# Blueshift_V3.net
KiCad netlist of a schematic drawn in EAGLE
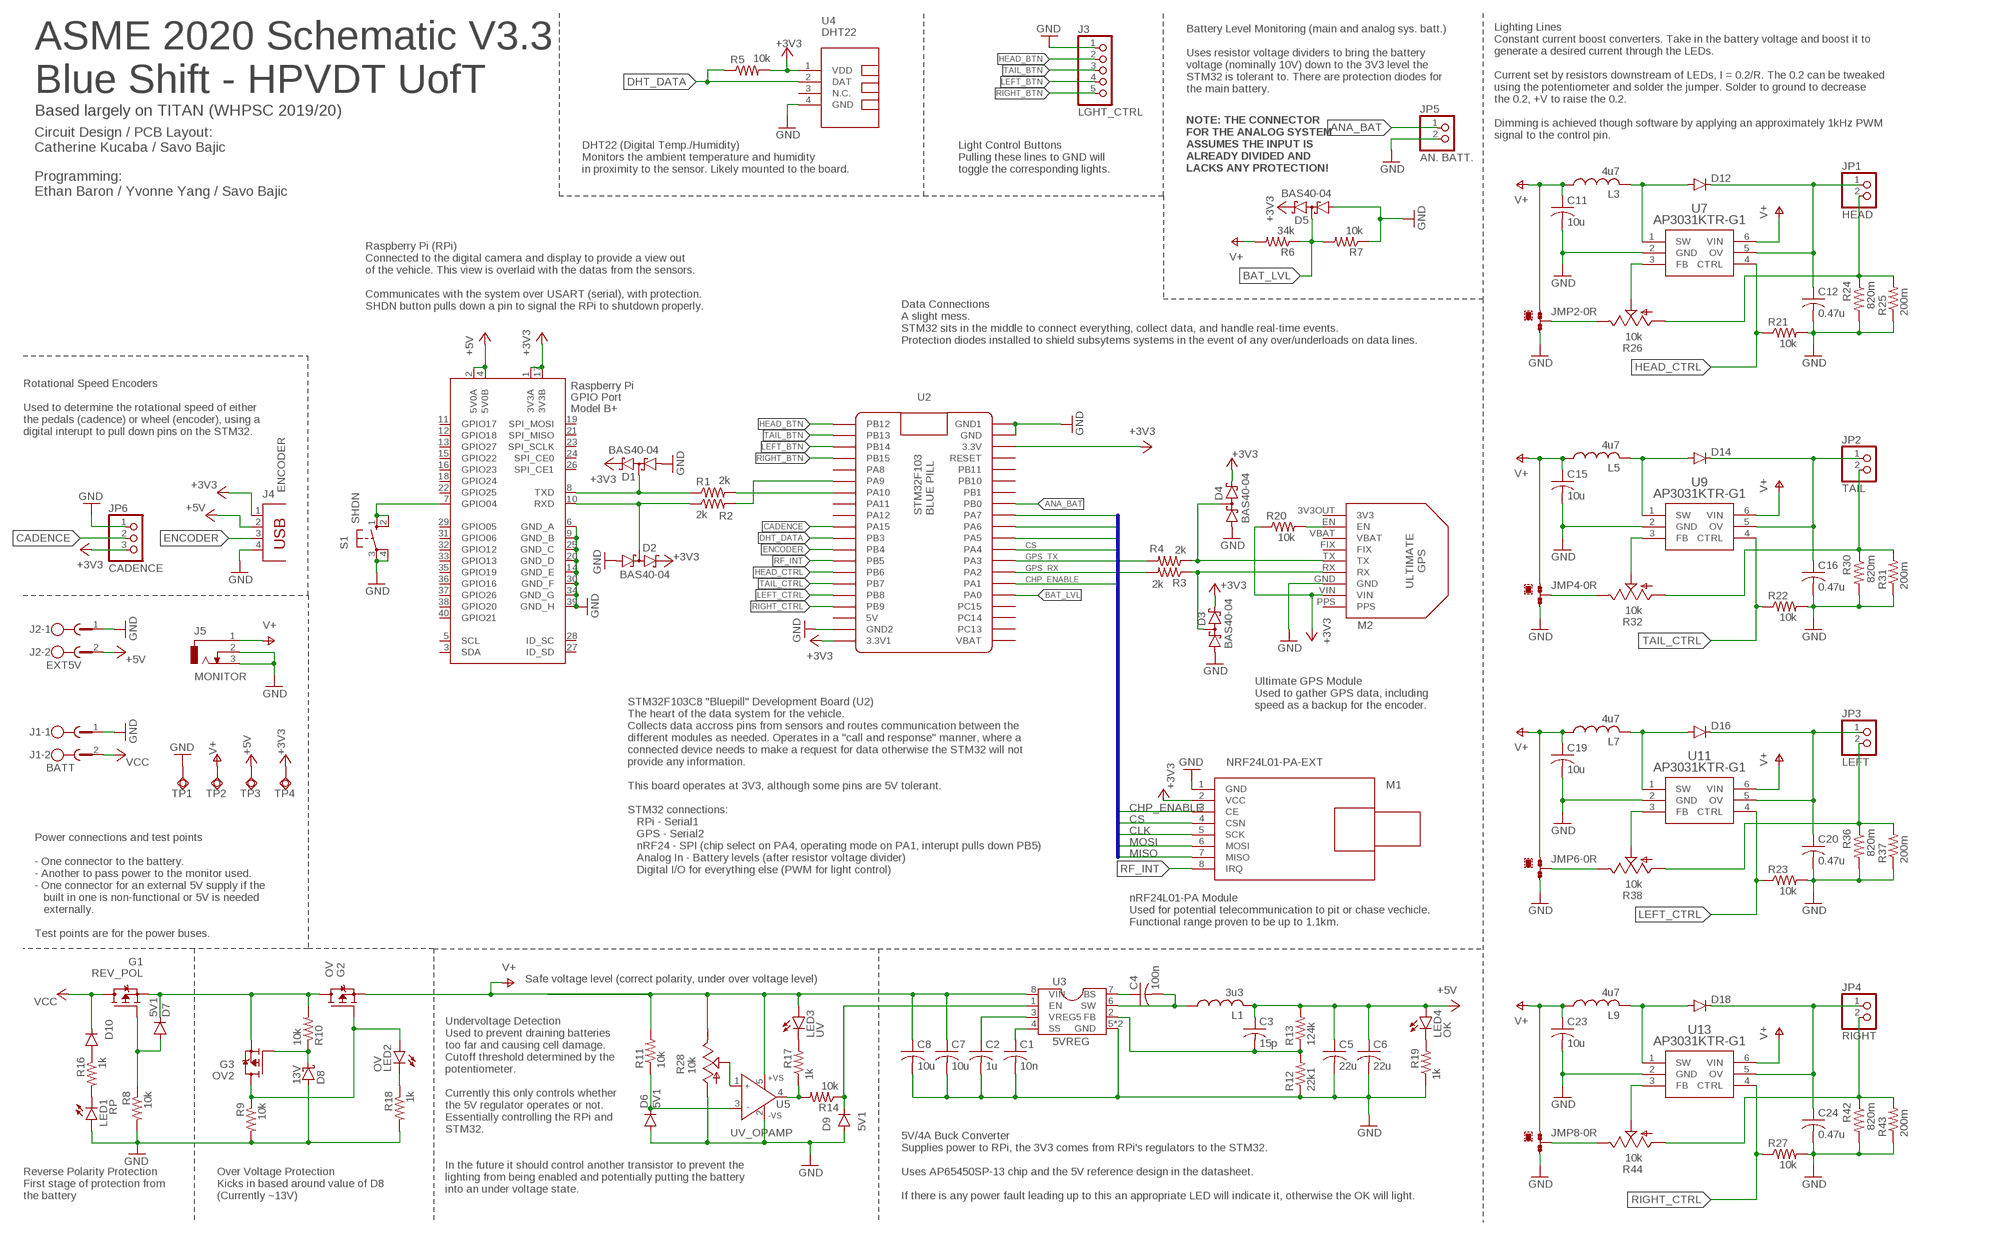
[diagram p0: schematic, sheet 1]

(export (version "E")
  (design (tool "Eeschema 10.0.6"))
  (components
    (comp (ref "C1")
      (value "10n")
      (footprint "eagle-import:C0402")
      (libsource (lib "eagle-import") (part "C-USC0402"))
    )
    (comp (ref "C2")
      (value "1u")
      (footprint "eagle-import:C0402")
      (libsource (lib "eagle-import") (part "C-USC0402"))
    )
    (comp (ref "C3")
      (value "15p")
      (footprint "eagle-import:C0402")
      (libsource (lib "eagle-import") (part "C-USC0402"))
    )
    (comp (ref "C4")
      (value "100n")
      (footprint "eagle-import:C0402")
      (libsource (lib "eagle-import") (part "C-USC0402"))
    )
    (comp (ref "C5")
      (value "22u")
      (footprint "eagle-import:C0805")
      (libsource (lib "eagle-import") (part "C-USC0805"))
    )
    (comp (ref "C6")
      (value "22u")
      (footprint "eagle-import:C0805")
      (libsource (lib "eagle-import") (part "C-USC0805"))
    )
    (comp (ref "C7")
      (value "10u")
      (footprint "eagle-import:C0805")
      (libsource (lib "eagle-import") (part "C-USC0805"))
    )
    (comp (ref "C8")
      (value "10u")
      (footprint "eagle-import:C0805")
      (libsource (lib "eagle-import") (part "C-USC0805"))
    )
    (comp (ref "C11")
      (value "10u")
      (footprint "eagle-import:C1206K")
      (libsource (lib "eagle-import") (part "C-USC1206K"))
    )
    (comp (ref "C12")
      (value "0.47u")
      (footprint "eagle-import:C1206K")
      (libsource (lib "eagle-import") (part "C-USC1206K"))
    )
    (comp (ref "C15")
      (value "10u")
      (footprint "eagle-import:C1206K")
      (libsource (lib "eagle-import") (part "C-USC1206K"))
    )
    (comp (ref "C16")
      (value "0.47u")
      (footprint "eagle-import:C1206K")
      (libsource (lib "eagle-import") (part "C-USC1206K"))
    )
    (comp (ref "C19")
      (value "10u")
      (footprint "eagle-import:C1206K")
      (libsource (lib "eagle-import") (part "C-USC1206K"))
    )
    (comp (ref "C20")
      (value "0.47u")
      (footprint "eagle-import:C1206K")
      (libsource (lib "eagle-import") (part "C-USC1206K"))
    )
    (comp (ref "C23")
      (value "10u")
      (footprint "eagle-import:C1206K")
      (libsource (lib "eagle-import") (part "C-USC1206K"))
    )
    (comp (ref "C24")
      (value "0.47u")
      (footprint "eagle-import:C1206K")
      (libsource (lib "eagle-import") (part "C-USC1206K"))
    )
    (comp (ref "D1")
      (value "BAS40-04")
      (footprint "eagle-import:SOT23")
      (libsource (lib "eagle-import") (part "BAS40-04"))
    )
    (comp (ref "D2")
      (value "BAS40-04")
      (footprint "eagle-import:SOT23")
      (libsource (lib "eagle-import") (part "BAS40-04"))
    )
    (comp (ref "D3")
      (value "BAS40-04")
      (footprint "eagle-import:SOT23")
      (libsource (lib "eagle-import") (part "BAS40-04"))
    )
    (comp (ref "D4")
      (value "BAS40-04")
      (footprint "eagle-import:SOT23")
      (libsource (lib "eagle-import") (part "BAS40-04"))
    )
    (comp (ref "D5")
      (value "BAS40-04")
      (footprint "eagle-import:SOT23")
      (libsource (lib "eagle-import") (part "BAS40-04"))
    )
    (comp (ref "D6")
      (value "5V1")
      (footprint "eagle-import:SOD323-R")
      (libsource (lib "eagle-import") (part "DIODE-SOD323-R"))
    )
    (comp (ref "D7")
      (value "5V1")
      (footprint "eagle-import:SOD323-R")
      (libsource (lib "eagle-import") (part "DIODE-SOD323-R"))
    )
    (comp (ref "D8")
      (value "13V")
      (footprint "eagle-import:SOT23")
      (libsource (lib "eagle-import") (part "BAS70"))
    )
    (comp (ref "D9")
      (value "5V1")
      (footprint "eagle-import:SOD323-R")
      (libsource (lib "eagle-import") (part "DIODE-SOD323-R"))
    )
    (comp (ref "D10")
      (value "DIODE-SOD80C")
      (footprint "eagle-import:SOD80C")
      (libsource (lib "eagle-import") (part "DIODE-SOD80C"))
    )
    (comp (ref "D12")
      (value "DIODE-DO-214AC")
      (footprint "eagle-import:DO-214AC")
      (libsource (lib "eagle-import") (part "DIODE-DO-214AC"))
    )
    (comp (ref "D14")
      (value "DIODE-DO-214AC")
      (footprint "eagle-import:DO-214AC")
      (libsource (lib "eagle-import") (part "DIODE-DO-214AC"))
    )
    (comp (ref "D16")
      (value "DIODE-DO-214AC")
      (footprint "eagle-import:DO-214AC")
      (libsource (lib "eagle-import") (part "DIODE-DO-214AC"))
    )
    (comp (ref "D18")
      (value "DIODE-DO-214AC")
      (footprint "eagle-import:DO-214AC")
      (libsource (lib "eagle-import") (part "DIODE-DO-214AC"))
    )
    (comp (ref "G1")
      (value "REV_POL")
      (footprint "eagle-import:TSOP-6")
      (libsource (lib "eagle-import") (part "SI3493DDV-T1-GE3"))
    )
    (comp (ref "G2")
      (value "OV")
      (footprint "eagle-import:TSOP-6")
      (libsource (lib "eagle-import") (part "SI3493DDV-T1-GE3"))
    )
    (comp (ref "G3")
      (value "OV2")
      (footprint "eagle-import:TSOP-6")
      (libsource (lib "eagle-import") (part "SI3493DDV-T1-GE3"))
    )
    (comp (ref "J1")
      (value "BATT")
      (footprint "eagle-import:MSTBV2")
      (libsource (lib "eagle-import") (part "MST2V"))
    )
    (comp (ref "J2")
      (value "EXT5V")
      (footprint "eagle-import:MSTBV2")
      (libsource (lib "eagle-import") (part "MST2V"))
    )
    (comp (ref "J3")
      (value "LGHT_CTRL")
      (footprint "eagle-import:1X05")
      (libsource (lib "eagle-import") (part "PINHD-1X5"))
    )
    (comp (ref "J4")
      (value "ENCODER")
      (footprint "eagle-import:PN87520")
      (libsource (lib "eagle-import") (part "PN87520"))
    )
    (comp (ref "J5")
      (value "MONITOR")
      (footprint "eagle-import:DCJ0303")
      (libsource (lib "eagle-import") (part "DCJ0303"))
    )
    (comp (ref "JMP2")
      (value "0R-JUMPA")
      (footprint "eagle-import:A0R-JMP")
      (libsource (lib "eagle-import") (part "0R-JUMPA"))
    )
    (comp (ref "JMP4")
      (value "0R-JUMPA")
      (footprint "eagle-import:A0R-JMP")
      (libsource (lib "eagle-import") (part "0R-JUMPA"))
    )
    (comp (ref "JMP6")
      (value "0R-JUMPA")
      (footprint "eagle-import:A0R-JMP")
      (libsource (lib "eagle-import") (part "0R-JUMPA"))
    )
    (comp (ref "JMP8")
      (value "0R-JUMPA")
      (footprint "eagle-import:A0R-JMP")
      (libsource (lib "eagle-import") (part "0R-JUMPA"))
    )
    (comp (ref "JP1")
      (value "HEAD")
      (footprint "eagle-import:1X02")
      (libsource (lib "eagle-import") (part "PINHD-1X2"))
    )
    (comp (ref "JP2")
      (value "TAIL")
      (footprint "eagle-import:1X02")
      (libsource (lib "eagle-import") (part "PINHD-1X2"))
    )
    (comp (ref "JP3")
      (value "LEFT")
      (footprint "eagle-import:1X02")
      (libsource (lib "eagle-import") (part "PINHD-1X2"))
    )
    (comp (ref "JP4")
      (value "RIGHT")
      (footprint "eagle-import:1X02")
      (libsource (lib "eagle-import") (part "PINHD-1X2"))
    )
    (comp (ref "JP5")
      (value "AN. BATT.")
      (footprint "eagle-import:1X02")
      (libsource (lib "eagle-import") (part "PINHD-1X2"))
    )
    (comp (ref "JP6")
      (value "CADENCE")
      (footprint "eagle-import:1X03")
      (libsource (lib "eagle-import") (part "PINHD-1X3"))
    )
    (comp (ref "L1")
      (value "3u3")
      (footprint "eagle-import:SDES064T")
      (libsource (lib "eagle-import") (part "SDES064T-3R3MS"))
    )
    (comp (ref "L3")
      (value "4u7")
      (footprint "eagle-import:INDDFN600X600X280-2N")
      (libsource (lib "eagle-import") (part "NR6028NR6028"))
    )
    (comp (ref "L5")
      (value "4u7")
      (footprint "eagle-import:INDDFN600X600X280-2N")
      (libsource (lib "eagle-import") (part "NR6028NR6028"))
    )
    (comp (ref "L7")
      (value "4u7")
      (footprint "eagle-import:INDDFN600X600X280-2N")
      (libsource (lib "eagle-import") (part "NR6028NR6028"))
    )
    (comp (ref "L9")
      (value "4u7")
      (footprint "eagle-import:INDDFN600X600X280-2N")
      (libsource (lib "eagle-import") (part "NR6028NR6028"))
    )
    (comp (ref "LED1")
      (value "RP")
      (footprint "eagle-import:SML0805")
      (libsource (lib "eagle-import") (part "LEDSML0805"))
    )
    (comp (ref "LED2")
      (value "OV")
      (footprint "eagle-import:SML0805")
      (libsource (lib "eagle-import") (part "LEDSML0805"))
    )
    (comp (ref "LED3")
      (value "UV")
      (footprint "eagle-import:SML0805")
      (libsource (lib "eagle-import") (part "LEDSML0805"))
    )
    (comp (ref "LED4")
      (value "OK")
      (footprint "eagle-import:SML0805")
      (libsource (lib "eagle-import") (part "LEDSML0805"))
    )
    (comp (ref "M1")
      (value "NRF24L01-PA-EXT")
      (footprint "eagle-import:WIRELESS-NRF24L01-PA-EXT")
      (libsource (lib "eagle-import") (part "WIRELESS-NRF24L01-PA-EXT"))
    )
    (comp (ref "M2")
      (value "ULTIMATE-GPS")
      (footprint "eagle-import:ULTIMATE_GPS")
      (libsource (lib "eagle-import") (part "ULTIMATE-GPS"))
    )
    (comp (ref "R1")
      (value "2k")
      (footprint "eagle-import:R0402")
      (libsource (lib "eagle-import") (part "R-US_R0402"))
    )
    (comp (ref "R2")
      (value "2k")
      (footprint "eagle-import:R0402")
      (libsource (lib "eagle-import") (part "R-US_R0402"))
    )
    (comp (ref "R3")
      (value "2k")
      (footprint "eagle-import:R0402")
      (libsource (lib "eagle-import") (part "R-US_R0402"))
    )
    (comp (ref "R4")
      (value "2k")
      (footprint "eagle-import:R0402")
      (libsource (lib "eagle-import") (part "R-US_R0402"))
    )
    (comp (ref "R5")
      (value "10k")
      (footprint "eagle-import:R0402")
      (libsource (lib "eagle-import") (part "R-US_R0402"))
    )
    (comp (ref "R6")
      (value "34k")
      (footprint "eagle-import:R0402")
      (libsource (lib "eagle-import") (part "R-US_R0402"))
    )
    (comp (ref "R7")
      (value "10k")
      (footprint "eagle-import:R0402")
      (libsource (lib "eagle-import") (part "R-US_R0402"))
    )
    (comp (ref "R8")
      (value "10k")
      (footprint "eagle-import:R0402")
      (libsource (lib "eagle-import") (part "R-US_R0402"))
    )
    (comp (ref "R9")
      (value "10k")
      (footprint "eagle-import:R0402")
      (libsource (lib "eagle-import") (part "R-US_R0402"))
    )
    (comp (ref "R10")
      (value "10k")
      (footprint "eagle-import:R0402")
      (libsource (lib "eagle-import") (part "R-US_R0402"))
    )
    (comp (ref "R11")
      (value "10k")
      (footprint "eagle-import:R0402")
      (libsource (lib "eagle-import") (part "R-US_R0402"))
    )
    (comp (ref "R12")
      (value "22k1")
      (footprint "eagle-import:R0402")
      (libsource (lib "eagle-import") (part "R-US_R0402"))
    )
    (comp (ref "R13")
      (value "124k")
      (footprint "eagle-import:R0402")
      (libsource (lib "eagle-import") (part "R-US_R0402"))
    )
    (comp (ref "R14")
      (value "10k")
      (footprint "eagle-import:R0402")
      (libsource (lib "eagle-import") (part "R-US_R0402"))
    )
    (comp (ref "R16")
      (value "1k")
      (footprint "eagle-import:R0402")
      (libsource (lib "eagle-import") (part "R-US_R0402"))
    )
    (comp (ref "R17")
      (value "1k")
      (footprint "eagle-import:R0402")
      (libsource (lib "eagle-import") (part "R-US_R0402"))
    )
    (comp (ref "R18")
      (value "1k")
      (footprint "eagle-import:R0402")
      (libsource (lib "eagle-import") (part "R-US_R0402"))
    )
    (comp (ref "R19")
      (value "1k")
      (footprint "eagle-import:R0402")
      (libsource (lib "eagle-import") (part "R-US_R0402"))
    )
    (comp (ref "R20")
      (value "10k")
      (footprint "eagle-import:R0402")
      (libsource (lib "eagle-import") (part "R-US_R0402"))
    )
    (comp (ref "R21")
      (value "10k")
      (footprint "eagle-import:R0402")
      (libsource (lib "eagle-import") (part "R-US_R0402"))
    )
    (comp (ref "R22")
      (value "10k")
      (footprint "eagle-import:R0402")
      (libsource (lib "eagle-import") (part "R-US_R0402"))
    )
    (comp (ref "R23")
      (value "10k")
      (footprint "eagle-import:R0402")
      (libsource (lib "eagle-import") (part "R-US_R0402"))
    )
    (comp (ref "R24")
      (value "820m")
      (footprint "eagle-import:R0603")
      (libsource (lib "eagle-import") (part "R-US_R0603"))
    )
    (comp (ref "R25")
      (value "200m")
      (footprint "eagle-import:R0805")
      (libsource (lib "eagle-import") (part "R-US_R0805"))
    )
    (comp (ref "R26")
      (value "10k")
      (footprint "eagle-import:RJ9W")
      (libsource (lib "eagle-import") (part "TRIM_US-RJ9W"))
    )
    (comp (ref "R27")
      (value "10k")
      (footprint "eagle-import:R0402")
      (libsource (lib "eagle-import") (part "R-US_R0402"))
    )
    (comp (ref "R28")
      (value "10k")
      (footprint "eagle-import:RJ9W")
      (libsource (lib "eagle-import") (part "TRIM_US-RJ9W"))
    )
    (comp (ref "R30")
      (value "820m")
      (footprint "eagle-import:R0603")
      (libsource (lib "eagle-import") (part "R-US_R0603"))
    )
    (comp (ref "R31")
      (value "200m")
      (footprint "eagle-import:R0805")
      (libsource (lib "eagle-import") (part "R-US_R0805"))
    )
    (comp (ref "R32")
      (value "10k")
      (footprint "eagle-import:RJ9W")
      (libsource (lib "eagle-import") (part "TRIM_US-RJ9W"))
    )
    (comp (ref "R36")
      (value "820m")
      (footprint "eagle-import:R0603")
      (libsource (lib "eagle-import") (part "R-US_R0603"))
    )
    (comp (ref "R37")
      (value "200m")
      (footprint "eagle-import:R0805")
      (libsource (lib "eagle-import") (part "R-US_R0805"))
    )
    (comp (ref "R38")
      (value "10k")
      (footprint "eagle-import:RJ9W")
      (libsource (lib "eagle-import") (part "TRIM_US-RJ9W"))
    )
    (comp (ref "R42")
      (value "820m")
      (footprint "eagle-import:R0603")
      (libsource (lib "eagle-import") (part "R-US_R0603"))
    )
    (comp (ref "R43")
      (value "200m")
      (footprint "eagle-import:R0805")
      (libsource (lib "eagle-import") (part "R-US_R0805"))
    )
    (comp (ref "R44")
      (value "10k")
      (footprint "eagle-import:RJ9W")
      (libsource (lib "eagle-import") (part "TRIM_US-RJ9W"))
    )
    (comp (ref "S1")
      (value "SHDN")
      (footprint "eagle-import:B3F-10XX")
      (fields (field (name "MPN") "B3F-1000"))
      (libsource (lib "eagle-import") (part "10-XX"))
    )
    (comp (ref "TP1")
      (value "TPSQTP20SQ")
      (footprint "eagle-import:TP20SQ")
      (libsource (lib "eagle-import") (part "TPSQTP20SQ"))
    )
    (comp (ref "TP2")
      (value "TPSQTP20R")
      (footprint "eagle-import:TP20R")
      (libsource (lib "eagle-import") (part "TPSQTP20R"))
    )
    (comp (ref "TP3")
      (value "TPSQTP20R")
      (footprint "eagle-import:TP20R")
      (libsource (lib "eagle-import") (part "TPSQTP20R"))
    )
    (comp (ref "TP4")
      (value "TPSQTP20R")
      (footprint "eagle-import:TP20R")
      (libsource (lib "eagle-import") (part "TPSQTP20R"))
    )
    (comp (ref "U1")
      (value "RASPI_HAT")
      (footprint "eagle-import:RASPI_BOARD_B+HAT_CF")
      (libsource (lib "eagle-import") (part "RASPI_HAT"))
    )
    (comp (ref "U2")
      (value "BLUEPILL")
      (footprint "eagle-import:BLUE_PILL")
      (libsource (lib "eagle-import") (part "BLUE_PILL"))
    )
    (comp (ref "U3")
      (value "5VREG")
      (footprint "eagle-import:SO-8EP")
      (libsource (lib "eagle-import") (part "AP65450SP-13"))
    )
    (comp (ref "U4")
      (value "DHT22")
      (footprint "eagle-import:TEMP-HUM-SENSOR-DHT22")
      (libsource (lib "eagle-import") (part "TEMP-HUM-SENSOR-DHT22"))
    )
    (comp (ref "U5")
      (value "UV_OPAMP")
      (footprint "eagle-import:SOT-753")
      (libsource (lib "eagle-import") (part "TA75S558F,LF"))
    )
    (comp (ref "U7")
      (value "AP3031KTR-G1")
      (footprint "eagle-import:SOT23-6")
      (fields (field (name "MANUFACTURER_PART_NUMBER") "AP3031KTRG1"))
      (libsource (lib "eagle-import") (part "AP3031KTR-G1"))
    )
    (comp (ref "U9")
      (value "AP3031KTR-G1")
      (footprint "eagle-import:SOT23-6")
      (fields (field (name "MANUFACTURER_PART_NUMBER") "AP3031KTRG1"))
      (libsource (lib "eagle-import") (part "AP3031KTR-G1"))
    )
    (comp (ref "U11")
      (value "AP3031KTR-G1")
      (footprint "eagle-import:SOT23-6")
      (fields (field (name "MANUFACTURER_PART_NUMBER") "AP3031KTRG1"))
      (libsource (lib "eagle-import") (part "AP3031KTR-G1"))
    )
    (comp (ref "U13")
      (value "AP3031KTR-G1")
      (footprint "eagle-import:SOT23-6")
      (fields (field (name "MANUFACTURER_PART_NUMBER") "AP3031KTRG1"))
      (libsource (lib "eagle-import") (part "AP3031KTR-G1"))
    )
  )
  (nets
    (net (code "1") (name "+3V3") (class "Default")
      (node (ref "D1") (pin "2") (pinfunction "C2_2") (pintype "passive"))
      (node (ref "D2") (pin "2") (pinfunction "C2_2") (pintype "passive"))
      (node (ref "D3") (pin "2") (pinfunction "C2_2") (pintype "passive"))
      (node (ref "D4") (pin "2") (pinfunction "C2_2") (pintype "passive"))
      (node (ref "D5") (pin "2") (pinfunction "C2_2") (pintype "passive"))
      (node (ref "J4") (pin "1") (pinfunction "1_1") (pintype "passive"))
      (node (ref "JP6") (pin "3") (pinfunction "3_3") (pintype "passive"))
      (node (ref "M1") (pin "2") (pinfunction "VCC_2") (pintype "power_in"))
      (node (ref "M2") (pin "VIN") (pinfunction "VIN_VIN") (pintype "power_in"))
      (node (ref "R20") (pin "1") (pinfunction "1_1") (pintype "passive"))
      (node (ref "R5") (pin "2") (pinfunction "2_2") (pintype "passive"))
      (node (ref "TP4") (pin "TP") (pinfunction "TP_TP") (pintype "input"))
      (node (ref "U1") (pin "1") (pinfunction "3V3A_1") (pintype "power_in"))
      (node (ref "U1") (pin "17") (pinfunction "3V3B_17") (pintype "power_in"))
      (node (ref "U2") (pin "P$20") (pinfunction "3.3V1_P$20") (pintype "bidirectional"))
      (node (ref "U2") (pin "P$23") (pinfunction "3.3V_P$23") (pintype "bidirectional"))
      (node (ref "U4") (pin "1") (pinfunction "VDD_1") (pintype "power_in"))
    )
    (net (code "2") (name "+5V") (class "Default")
      (node (ref "C3") (pin "1") (pinfunction "1_1") (pintype "passive"))
      (node (ref "C5") (pin "1") (pinfunction "1_1") (pintype "passive"))
      (node (ref "C6") (pin "1") (pinfunction "1_1") (pintype "passive"))
      (node (ref "J2") (pin "2") (pinfunction "1_2") (pintype "passive"))
      (node (ref "J4") (pin "2") (pinfunction "2_2") (pintype "passive"))
      (node (ref "L1") (pin "2") (pinfunction "2_2") (pintype "passive"))
      (node (ref "LED4") (pin "A") (pinfunction "A_A") (pintype "passive"))
      (node (ref "R13") (pin "2") (pinfunction "2_2") (pintype "passive"))
      (node (ref "TP3") (pin "TP") (pinfunction "TP_TP") (pintype "input"))
      (node (ref "U1") (pin "2") (pinfunction "5V0A_2") (pintype "power_in"))
      (node (ref "U1") (pin "4") (pinfunction "5V0B_4") (pintype "power_in"))
    )
    (net (code "3") (name "/CHP_ENABLE") (class "Default")
      (node (ref "M1") (pin "3") (pinfunction "CE_3") (pintype "bidirectional"))
      (node (ref "U2") (pin "P$35") (pinfunction "PA1_P$35") (pintype "bidirectional"))
    )
    (net (code "4") (name "/CLK") (class "Default")
      (node (ref "M1") (pin "5") (pinfunction "SCK_5") (pintype "bidirectional"))
      (node (ref "U2") (pin "P$31") (pinfunction "PA5_P$31") (pintype "bidirectional"))
    )
    (net (code "5") (name "/CS") (class "Default")
      (node (ref "M1") (pin "4") (pinfunction "CSN_4") (pintype "bidirectional"))
      (node (ref "U2") (pin "P$32") (pinfunction "PA4_P$32") (pintype "bidirectional"))
    )
    (net (code "6") (name "/GPS_RX") (class "Default")
      (node (ref "R3") (pin "2") (pinfunction "2_2") (pintype "passive"))
      (node (ref "U2") (pin "P$34") (pinfunction "PA2_P$34") (pintype "bidirectional"))
    )
    (net (code "7") (name "/GPS_TX") (class "Default")
      (node (ref "R4") (pin "2") (pinfunction "2_2") (pintype "passive"))
      (node (ref "U2") (pin "P$33") (pinfunction "PA3_P$33") (pintype "bidirectional"))
    )
    (net (code "8") (name "/MISO") (class "Default")
      (node (ref "M1") (pin "7") (pinfunction "MISO_7") (pintype "bidirectional"))
      (node (ref "U2") (pin "P$30") (pinfunction "PA6_P$30") (pintype "bidirectional"))
    )
    (net (code "9") (name "/MOSI") (class "Default")
      (node (ref "M1") (pin "6") (pinfunction "MOSI_6") (pintype "bidirectional"))
      (node (ref "U2") (pin "P$29") (pinfunction "PA7_P$29") (pintype "bidirectional"))
    )
    (net (code "10") (name "ANA_BAT") (class "Default")
      (node (ref "JP5") (pin "1") (pinfunction "1_1") (pintype "passive"))
      (node (ref "U2") (pin "P$28") (pinfunction "PB0_P$28") (pintype "bidirectional"))
    )
    (net (code "11") (name "BAT_LVL") (class "Default")
      (node (ref "D5") (pin "3") (pinfunction "C1A2_3") (pintype "passive"))
      (node (ref "R6") (pin "1") (pinfunction "1_1") (pintype "passive"))
      (node (ref "R7") (pin "2") (pinfunction "2_2") (pintype "passive"))
      (node (ref "U2") (pin "P$36") (pinfunction "PA0_P$36") (pintype "bidirectional"))
    )
    (net (code "12") (name "CADENCE") (class "Default")
      (node (ref "JP6") (pin "2") (pinfunction "2_2") (pintype "passive"))
      (node (ref "U2") (pin "P$10") (pinfunction "PA15_P$10") (pintype "bidirectional"))
    )
    (net (code "13") (name "DHT_DATA") (class "Default")
      (node (ref "R5") (pin "1") (pinfunction "1_1") (pintype "passive"))
      (node (ref "U2") (pin "P$11") (pinfunction "PB3_P$11") (pintype "bidirectional"))
      (node (ref "U4") (pin "2") (pinfunction "DAT_2") (pintype "bidirectional"))
    )
    (net (code "14") (name "ENCODER") (class "Default")
      (node (ref "J4") (pin "3") (pinfunction "3_3") (pintype "passive"))
      (node (ref "U2") (pin "P$12") (pinfunction "PB4_P$12") (pintype "bidirectional"))
    )
    (net (code "15") (name "GND") (class "Default")
      (node (ref "C1") (pin "2") (pinfunction "2_2") (pintype "passive"))
      (node (ref "C11") (pin "2") (pinfunction "2_2") (pintype "passive"))
      (node (ref "C12") (pin "2") (pinfunction "2_2") (pintype "passive"))
      (node (ref "C15") (pin "2") (pinfunction "2_2") (pintype "passive"))
      (node (ref "C16") (pin "2") (pinfunction "2_2") (pintype "passive"))
      (node (ref "C19") (pin "2") (pinfunction "2_2") (pintype "passive"))
      (node (ref "C2") (pin "2") (pinfunction "2_2") (pintype "passive"))
      (node (ref "C20") (pin "2") (pinfunction "2_2") (pintype "passive"))
      (node (ref "C23") (pin "2") (pinfunction "2_2") (pintype "passive"))
      (node (ref "C24") (pin "2") (pinfunction "2_2") (pintype "passive"))
      (node (ref "C5") (pin "2") (pinfunction "2_2") (pintype "passive"))
      (node (ref "C6") (pin "2") (pinfunction "2_2") (pintype "passive"))
      (node (ref "C7") (pin "2") (pinfunction "2_2") (pintype "passive"))
      (node (ref "C8") (pin "2") (pinfunction "2_2") (pintype "passive"))
      (node (ref "D1") (pin "1") (pinfunction "A1_1") (pintype "passive"))
      (node (ref "D2") (pin "1") (pinfunction "A1_1") (pintype "passive"))
      (node (ref "D3") (pin "1") (pinfunction "A1_1") (pintype "passive"))
      (node (ref "D4") (pin "1") (pinfunction "A1_1") (pintype "passive"))
      (node (ref "D5") (pin "1") (pinfunction "A1_1") (pintype "passive"))
      (node (ref "D6") (pin "A") (pinfunction "A_A") (pintype "passive"))
      (node (ref "D8") (pin "1") (pinfunction "A_1") (pintype "passive"))
      (node (ref "D9") (pin "A") (pinfunction "A_A") (pintype "passive"))
      (node (ref "J1") (pin "1") (pinfunction "1_1") (pintype "passive"))
      (node (ref "J2") (pin "1") (pinfunction "1_1") (pintype "passive"))
      (node (ref "J3") (pin "1") (pinfunction "1_1") (pintype "passive"))
      (node (ref "J4") (pin "4") (pinfunction "4_4") (pintype "passive"))
      (node (ref "J5") (pin "2") (pinfunction "2_2") (pintype "passive"))
      (node (ref "J5") (pin "3") (pinfunction "3_3") (pintype "passive"))
      (node (ref "JMP2") (pin "3") (pinfunction "3_3") (pintype "passive"))
      (node (ref "JMP4") (pin "3") (pinfunction "3_3") (pintype "passive"))
      (node (ref "JMP6") (pin "3") (pinfunction "3_3") (pintype "passive"))
      (node (ref "JMP8") (pin "3") (pinfunction "3_3") (pintype "passive"))
      (node (ref "JP5") (pin "2") (pinfunction "2_2") (pintype "passive"))
      (node (ref "JP6") (pin "1") (pinfunction "1_1") (pintype "passive"))
      (node (ref "LED1") (pin "A") (pinfunction "A_A") (pintype "passive"))
      (node (ref "M1") (pin "1") (pinfunction "GND_1") (pintype "power_in"))
      (node (ref "M2") (pin "GND") (pinfunction "GND_GND") (pintype "power_in"))
      (node (ref "R12") (pin "1") (pinfunction "1_1") (pintype "passive"))
      (node (ref "R18") (pin "2") (pinfunction "2_2") (pintype "passive"))
      (node (ref "R19") (pin "1") (pinfunction "1_1") (pintype "passive"))
      (node (ref "R21") (pin "2") (pinfunction "2_2") (pintype "passive"))
      (node (ref "R22") (pin "2") (pinfunction "2_2") (pintype "passive"))
      (node (ref "R23") (pin "2") (pinfunction "2_2") (pintype "passive"))
      (node (ref "R24") (pin "2") (pinfunction "2_2") (pintype "passive"))
      (node (ref "R25") (pin "1") (pinfunction "1_1") (pintype "passive"))
      (node (ref "R27") (pin "2") (pinfunction "2_2") (pintype "passive"))
      (node (ref "R28") (pin "A") (pinfunction "A_A") (pintype "passive"))
      (node (ref "R30") (pin "2") (pinfunction "2_2") (pintype "passive"))
      (node (ref "R31") (pin "1") (pinfunction "1_1") (pintype "passive"))
      (node (ref "R36") (pin "2") (pinfunction "2_2") (pintype "passive"))
      (node (ref "R37") (pin "1") (pinfunction "1_1") (pintype "passive"))
      (node (ref "R42") (pin "2") (pinfunction "2_2") (pintype "passive"))
      (node (ref "R43") (pin "1") (pinfunction "1_1") (pintype "passive"))
      (node (ref "R7") (pin "1") (pinfunction "1_1") (pintype "passive"))
      (node (ref "R8") (pin "2") (pinfunction "2_2") (pintype "passive"))
      (node (ref "R9") (pin "2") (pinfunction "2_2") (pintype "passive"))
      (node (ref "S1") (pin "3") (pinfunction "P_3") (pintype "passive"))
      (node (ref "S1") (pin "4") (pinfunction "P1_4") (pintype "passive"))
      (node (ref "TP1") (pin "TP") (pinfunction "TP_TP") (pintype "input"))
      (node (ref "U1") (pin "14") (pinfunction "GND_E_14") (pintype "power_in"))
      (node (ref "U1") (pin "20") (pinfunction "GND_D_20") (pintype "power_in"))
      (node (ref "U1") (pin "25") (pinfunction "GND_C_25") (pintype "power_in"))
      (node (ref "U1") (pin "30") (pinfunction "GND_F_30") (pintype "power_in"))
      (node (ref "U1") (pin "34") (pinfunction "GND_G_34") (pintype "power_in"))
      (node (ref "U1") (pin "39") (pinfunction "GND_H_39") (pintype "power_in"))
      (node (ref "U1") (pin "6") (pinfunction "GND_A_6") (pintype "power_in"))
      (node (ref "U1") (pin "9") (pinfunction "GND_B_9") (pintype "power_in"))
      (node (ref "U11") (pin "2") (pinfunction "GND_2") (pintype "power_in"))
      (node (ref "U13") (pin "2") (pinfunction "GND_2") (pintype "power_in"))
      (node (ref "U2") (pin "P$19") (pinfunction "GND2_P$19") (pintype "bidirectional"))
      (node (ref "U2") (pin "P$21") (pinfunction "GND1_P$21") (pintype "power_in"))
      (node (ref "U2") (pin "P$22") (pinfunction "GND_P$22") (pintype "bidirectional"))
      (node (ref "U3") (pin "5") (pinfunction "GND_5") (pintype "bidirectional"))
      (node (ref "U3") (pin "TP") (pinfunction "GND_TP") (pintype "bidirectional"))
      (node (ref "U4") (pin "4") (pinfunction "GND_4") (pintype "power_in"))
      (node (ref "U5") (pin "2") (pinfunction "-VS_2") (pintype "input"))
      (node (ref "U7") (pin "2") (pinfunction "GND_2") (pintype "power_in"))
      (node (ref "U9") (pin "2") (pinfunction "GND_2") (pintype "power_in"))
    )
    (net (code "16") (name "HEAD_BTN") (class "Default")
      (node (ref "J3") (pin "2") (pinfunction "2_2") (pintype "passive"))
      (node (ref "U2") (pin "P$1") (pinfunction "PB12_P$1") (pintype "bidirectional"))
    )
    (net (code "17") (name "HEAD_CTRL") (class "Default")
      (node (ref "R21") (pin "1") (pinfunction "1_1") (pintype "passive"))
      (node (ref "U2") (pin "P$14") (pinfunction "PB6_P$14") (pintype "bidirectional"))
      (node (ref "U7") (pin "4") (pinfunction "CTRL_4") (pintype "passive"))
    )
    (net (code "18") (name "LEFT_BTN") (class "Default")
      (node (ref "J3") (pin "4") (pinfunction "4_4") (pintype "passive"))
      (node (ref "U2") (pin "P$3") (pinfunction "PB14_P$3") (pintype "bidirectional"))
    )
    (net (code "19") (name "LEFT_CTRL") (class "Default")
      (node (ref "R23") (pin "1") (pinfunction "1_1") (pintype "passive"))
      (node (ref "U11") (pin "4") (pinfunction "CTRL_4") (pintype "passive"))
      (node (ref "U2") (pin "P$16") (pinfunction "PB8_P$16") (pintype "bidirectional"))
    )
    (net (code "20") (name "Net-(D1-C1A2)") (class "Default")
      (node (ref "D1") (pin "3") (pinfunction "C1A2_3") (pintype "passive"))
      (node (ref "R1") (pin "1") (pinfunction "1_1") (pintype "passive"))
      (node (ref "U1") (pin "8") (pinfunction "TXD_8") (pintype "bidirectional"))
    )
    (net (code "21") (name "Net-(D2-C1A2)") (class "Default")
      (node (ref "D2") (pin "3") (pinfunction "C1A2_3") (pintype "passive"))
      (node (ref "R2") (pin "1") (pinfunction "1_1") (pintype "passive"))
      (node (ref "U1") (pin "10") (pinfunction "RXD_10") (pintype "bidirectional"))
    )
    (net (code "22") (name "Net-(D3-C1A2)") (class "Default")
      (node (ref "D3") (pin "3") (pinfunction "C1A2_3") (pintype "passive"))
      (node (ref "M2") (pin "RX") (pinfunction "RX_RX") (pintype "input"))
      (node (ref "R3") (pin "1") (pinfunction "1_1") (pintype "passive"))
    )
    (net (code "23") (name "Net-(D4-C1A2)") (class "Default")
      (node (ref "D4") (pin "3") (pinfunction "C1A2_3") (pintype "passive"))
      (node (ref "M2") (pin "TX") (pinfunction "TX_TX") (pintype "output"))
      (node (ref "R4") (pin "1") (pinfunction "1_1") (pintype "passive"))
    )
    (net (code "24") (name "Net-(D8-C)") (class "Default")
      (node (ref "D8") (pin "3") (pinfunction "C_3") (pintype "passive"))
      (node (ref "G3") (pin "3") (pinfunction "G_3") (pintype "passive"))
      (node (ref "R10") (pin "1") (pinfunction "1_1") (pintype "passive"))
    )
    (net (code "25") (name "Net-(D10-PadA)") (class "Default")
      (node (ref "D10") (pin "A") (pinfunction "A_A") (pintype "passive"))
      (node (ref "R16") (pin "1") (pinfunction "1_1") (pintype "passive"))
    )
    (net (code "26") (name "Net-(G1-G)") (class "Default")
      (node (ref "D7") (pin "A") (pinfunction "A_A") (pintype "passive"))
      (node (ref "G1") (pin "3") (pinfunction "G_3") (pintype "passive"))
      (node (ref "R8") (pin "1") (pinfunction "1_1") (pintype "passive"))
    )
    (net (code "27") (name "Net-(G1-S)") (class "Default")
      (node (ref "D7") (pin "C") (pinfunction "C_C") (pintype "passive"))
      (node (ref "G1") (pin "4") (pinfunction "S_4") (pintype "passive"))
      (node (ref "G2") (pin "1") (pinfunction "D_1") (pintype "passive"))
      (node (ref "G2") (pin "2") (pinfunction "D_2") (pintype "passive"))
      (node (ref "G2") (pin "5") (pinfunction "D_5") (pintype "passive"))
      (node (ref "G2") (pin "6") (pinfunction "D_6") (pintype "passive"))
      (node (ref "G3") (pin "4") (pinfunction "S_4") (pintype "passive"))
      (node (ref "R10") (pin "2") (pinfunction "2_2") (pintype "passive"))
    )
    (net (code "28") (name "Net-(G2-G)") (class "Default")
      (node (ref "G2") (pin "3") (pinfunction "G_3") (pintype "passive"))
      (node (ref "G3") (pin "1") (pinfunction "D_1") (pintype "passive"))
      (node (ref "G3") (pin "2") (pinfunction "D_2") (pintype "passive"))
      (node (ref "G3") (pin "5") (pinfunction "D_5") (pintype "passive"))
      (node (ref "G3") (pin "6") (pinfunction "D_6") (pintype "passive"))
      (node (ref "LED2") (pin "A") (pinfunction "A_A") (pintype "passive"))
      (node (ref "R9") (pin "1") (pinfunction "1_1") (pintype "passive"))
    )
    (net (code "29") (name "Net-(JMP2-Pad2)") (class "Default")
      (node (ref "JMP2") (pin "2") (pinfunction "2_2") (pintype "passive"))
      (node (ref "R26") (pin "E") (pinfunction "E_E") (pintype "passive"))
    )
    (net (code "30") (name "Net-(JMP4-Pad2)") (class "Default")
      (node (ref "JMP4") (pin "2") (pinfunction "2_2") (pintype "passive"))
      (node (ref "R32") (pin "E") (pinfunction "E_E") (pintype "passive"))
    )
    (net (code "31") (name "Net-(JMP6-Pad2)") (class "Default")
      (node (ref "JMP6") (pin "2") (pinfunction "2_2") (pintype "passive"))
      (node (ref "R38") (pin "E") (pinfunction "E_E") (pintype "passive"))
    )
    (net (code "32") (name "Net-(JMP8-Pad2)") (class "Default")
      (node (ref "JMP8") (pin "2") (pinfunction "2_2") (pintype "passive"))
      (node (ref "R44") (pin "E") (pinfunction "E_E") (pintype "passive"))
    )
    (net (code "33") (name "Net-(JP1-Pad2)") (class "Default")
      (node (ref "JP1") (pin "2") (pinfunction "2_2") (pintype "passive"))
      (node (ref "R24") (pin "1") (pinfunction "1_1") (pintype "passive"))
      (node (ref "R25") (pin "2") (pinfunction "2_2") (pintype "passive"))
      (node (ref "R26") (pin "A") (pinfunction "A_A") (pintype "passive"))
    )
    (net (code "34") (name "Net-(JP2-Pad2)") (class "Default")
      (node (ref "JP2") (pin "2") (pinfunction "2_2") (pintype "passive"))
      (node (ref "R30") (pin "1") (pinfunction "1_1") (pintype "passive"))
      (node (ref "R31") (pin "2") (pinfunction "2_2") (pintype "passive"))
      (node (ref "R32") (pin "A") (pinfunction "A_A") (pintype "passive"))
    )
    (net (code "35") (name "Net-(JP3-Pad2)") (class "Default")
      (node (ref "JP3") (pin "2") (pinfunction "2_2") (pintype "passive"))
      (node (ref "R36") (pin "1") (pinfunction "1_1") (pintype "passive"))
      (node (ref "R37") (pin "2") (pinfunction "2_2") (pintype "passive"))
      (node (ref "R38") (pin "A") (pinfunction "A_A") (pintype "passive"))
    )
    (net (code "36") (name "Net-(JP4-Pad2)") (class "Default")
      (node (ref "JP4") (pin "2") (pinfunction "2_2") (pintype "passive"))
      (node (ref "R42") (pin "1") (pinfunction "1_1") (pintype "passive"))
      (node (ref "R43") (pin "2") (pinfunction "2_2") (pintype "passive"))
      (node (ref "R44") (pin "A") (pinfunction "A_A") (pintype "passive"))
    )
    (net (code "37") (name "Net-(LED1-PadC)") (class "Default")
      (node (ref "LED1") (pin "C") (pinfunction "C_C") (pintype "passive"))
      (node (ref "R16") (pin "2") (pinfunction "2_2") (pintype "passive"))
    )
    (net (code "38") (name "Net-(LED2-PadC)") (class "Default")
      (node (ref "LED2") (pin "C") (pinfunction "C_C") (pintype "passive"))
      (node (ref "R18") (pin "1") (pinfunction "1_1") (pintype "passive"))
    )
    (net (code "39") (name "Net-(LED3-PadC)") (class "Default")
      (node (ref "LED3") (pin "C") (pinfunction "C_C") (pintype "passive"))
      (node (ref "R17") (pin "2") (pinfunction "2_2") (pintype "passive"))
    )
    (net (code "40") (name "Net-(LED4-PadC)") (class "Default")
      (node (ref "LED4") (pin "C") (pinfunction "C_C") (pintype "passive"))
      (node (ref "R19") (pin "2") (pinfunction "2_2") (pintype "passive"))
    )
    (net (code "41") (name "Net-(M2-PadEN)") (class "Default")
      (node (ref "M2") (pin "EN") (pinfunction "EN_EN") (pintype "input"))
      (node (ref "R20") (pin "2") (pinfunction "2_2") (pintype "passive"))
    )
    (net (code "42") (name "Net-(S1-S)") (class "Default")
      (node (ref "S1") (pin "1") (pinfunction "S_1") (pintype "passive"))
      (node (ref "S1") (pin "2") (pinfunction "S1_2") (pintype "passive"))
      (node (ref "U1") (pin "7") (pinfunction "GPIO04_7") (pintype "bidirectional"))
    )
    (net (code "43") (name "Net-(U2-PA9)") (class "Default")
      (node (ref "R2") (pin "2") (pinfunction "2_2") (pintype "passive"))
      (node (ref "U2") (pin "P$6") (pinfunction "PA9_P$6") (pintype "bidirectional"))
    )
    (net (code "44") (name "Net-(U2-PA10)") (class "Default")
      (node (ref "R1") (pin "2") (pinfunction "2_2") (pintype "passive"))
      (node (ref "U2") (pin "P$7") (pinfunction "PA10_P$7") (pintype "bidirectional"))
    )
    (net (code "45") (name "Net-(U3-BS)") (class "Default")
      (node (ref "C4") (pin "1") (pinfunction "1_1") (pintype "passive"))
      (node (ref "U3") (pin "7") (pinfunction "BS_7") (pintype "bidirectional"))
    )
    (net (code "46") (name "Net-(U3-EN)") (class "Default")
      (node (ref "D9") (pin "C") (pinfunction "C_C") (pintype "passive"))
      (node (ref "R14") (pin "1") (pinfunction "1_1") (pintype "passive"))
      (node (ref "U3") (pin "1") (pinfunction "EN_1") (pintype "bidirectional"))
    )
    (net (code "47") (name "Net-(U3-FB)") (class "Default")
      (node (ref "C3") (pin "2") (pinfunction "2_2") (pintype "passive"))
      (node (ref "R12") (pin "2") (pinfunction "2_2") (pintype "passive"))
      (node (ref "R13") (pin "1") (pinfunction "1_1") (pintype "passive"))
      (node (ref "U3") (pin "2") (pinfunction "FB_2") (pintype "bidirectional"))
    )
    (net (code "48") (name "Net-(U3-SS)") (class "Default")
      (node (ref "C1") (pin "1") (pinfunction "1_1") (pintype "passive"))
      (node (ref "U3") (pin "4") (pinfunction "SS_4") (pintype "bidirectional"))
    )
    (net (code "49") (name "Net-(U3-SW)") (class "Default")
      (node (ref "C4") (pin "2") (pinfunction "2_2") (pintype "passive"))
      (node (ref "L1") (pin "1") (pinfunction "1_1") (pintype "passive"))
      (node (ref "U3") (pin "6") (pinfunction "SW_6") (pintype "bidirectional"))
    )
    (net (code "50") (name "Net-(U3-VREG5)") (class "Default")
      (node (ref "C2") (pin "1") (pinfunction "1_1") (pintype "passive"))
      (node (ref "U3") (pin "3") (pinfunction "VREG5_3") (pintype "bidirectional"))
    )
    (net (code "51") (name "Net-(U5-IN+)") (class "Default")
      (node (ref "R28") (pin "S") (pinfunction "S_S") (pintype "passive"))
      (node (ref "U5") (pin "1") (pinfunction "IN+_1") (pintype "input"))
    )
    (net (code "52") (name "Net-(U5-IN-)") (class "Default")
      (node (ref "D6") (pin "C") (pinfunction "C_C") (pintype "passive"))
      (node (ref "R11") (pin "1") (pinfunction "1_1") (pintype "passive"))
      (node (ref "U5") (pin "3") (pinfunction "IN-_3") (pintype "input"))
    )
    (net (code "53") (name "Net-(U5-OUT)") (class "Default")
      (node (ref "R14") (pin "2") (pinfunction "2_2") (pintype "passive"))
      (node (ref "R17") (pin "1") (pinfunction "1_1") (pintype "passive"))
      (node (ref "U5") (pin "4") (pinfunction "OUT_4") (pintype "output"))
    )
    (net (code "54") (name "Net-(U7-FB)") (class "Default")
      (node (ref "R26") (pin "S") (pinfunction "S_S") (pintype "passive"))
      (node (ref "U7") (pin "3") (pinfunction "FB_3") (pintype "output"))
    )
    (net (code "55") (name "Net-(U7-OV)") (class "Default")
      (node (ref "C12") (pin "1") (pinfunction "1_1") (pintype "passive"))
      (node (ref "D12") (pin "C") (pinfunction "C_C") (pintype "passive"))
      (node (ref "JP1") (pin "1") (pinfunction "1_1") (pintype "passive"))
      (node (ref "U7") (pin "5") (pinfunction "OV_5") (pintype "passive"))
    )
    (net (code "56") (name "Net-(U7-SW)") (class "Default")
      (node (ref "D12") (pin "A") (pinfunction "A_A") (pintype "passive"))
      (node (ref "L3") (pin "2") (pinfunction "2_2") (pintype "passive"))
      (node (ref "U7") (pin "1") (pinfunction "SW_1") (pintype "output"))
    )
    (net (code "57") (name "Net-(U9-FB)") (class "Default")
      (node (ref "R32") (pin "S") (pinfunction "S_S") (pintype "passive"))
      (node (ref "U9") (pin "3") (pinfunction "FB_3") (pintype "output"))
    )
    (net (code "58") (name "Net-(U9-OV)") (class "Default")
      (node (ref "C16") (pin "1") (pinfunction "1_1") (pintype "passive"))
      (node (ref "D14") (pin "C") (pinfunction "C_C") (pintype "passive"))
      (node (ref "JP2") (pin "1") (pinfunction "1_1") (pintype "passive"))
      (node (ref "U9") (pin "5") (pinfunction "OV_5") (pintype "passive"))
    )
    (net (code "59") (name "Net-(U9-SW)") (class "Default")
      (node (ref "D14") (pin "A") (pinfunction "A_A") (pintype "passive"))
      (node (ref "L5") (pin "2") (pinfunction "2_2") (pintype "passive"))
      (node (ref "U9") (pin "1") (pinfunction "SW_1") (pintype "output"))
    )
    (net (code "60") (name "Net-(U11-FB)") (class "Default")
      (node (ref "R38") (pin "S") (pinfunction "S_S") (pintype "passive"))
      (node (ref "U11") (pin "3") (pinfunction "FB_3") (pintype "output"))
    )
    (net (code "61") (name "Net-(U11-OV)") (class "Default")
      (node (ref "C20") (pin "1") (pinfunction "1_1") (pintype "passive"))
      (node (ref "D16") (pin "C") (pinfunction "C_C") (pintype "passive"))
      (node (ref "JP3") (pin "1") (pinfunction "1_1") (pintype "passive"))
      (node (ref "U11") (pin "5") (pinfunction "OV_5") (pintype "passive"))
    )
    (net (code "62") (name "Net-(U11-SW)") (class "Default")
      (node (ref "D16") (pin "A") (pinfunction "A_A") (pintype "passive"))
      (node (ref "L7") (pin "2") (pinfunction "2_2") (pintype "passive"))
      (node (ref "U11") (pin "1") (pinfunction "SW_1") (pintype "output"))
    )
    (net (code "63") (name "Net-(U13-FB)") (class "Default")
      (node (ref "R44") (pin "S") (pinfunction "S_S") (pintype "passive"))
      (node (ref "U13") (pin "3") (pinfunction "FB_3") (pintype "output"))
    )
    (net (code "64") (name "Net-(U13-OV)") (class "Default")
      (node (ref "C24") (pin "1") (pinfunction "1_1") (pintype "passive"))
      (node (ref "D18") (pin "C") (pinfunction "C_C") (pintype "passive"))
      (node (ref "JP4") (pin "1") (pinfunction "1_1") (pintype "passive"))
      (node (ref "U13") (pin "5") (pinfunction "OV_5") (pintype "passive"))
    )
    (net (code "65") (name "Net-(U13-SW)") (class "Default")
      (node (ref "D18") (pin "A") (pinfunction "A_A") (pintype "passive"))
      (node (ref "L9") (pin "2") (pinfunction "2_2") (pintype "passive"))
      (node (ref "U13") (pin "1") (pinfunction "SW_1") (pintype "output"))
    )
    (net (code "66") (name "RF_INT") (class "Default")
      (node (ref "M1") (pin "8") (pinfunction "IRQ_8") (pintype "bidirectional"))
      (node (ref "U2") (pin "P$13") (pinfunction "PB5_P$13") (pintype "bidirectional"))
    )
    (net (code "67") (name "RIGHT_BTN") (class "Default")
      (node (ref "J3") (pin "5") (pinfunction "5_5") (pintype "passive"))
      (node (ref "U2") (pin "P$4") (pinfunction "PB15_P$4") (pintype "bidirectional"))
    )
    (net (code "68") (name "RIGHT_CTRL") (class "Default")
      (node (ref "R27") (pin "1") (pinfunction "1_1") (pintype "passive"))
      (node (ref "U13") (pin "4") (pinfunction "CTRL_4") (pintype "passive"))
      (node (ref "U2") (pin "P$17") (pinfunction "PB9_P$17") (pintype "bidirectional"))
    )
    (net (code "69") (name "TAIL_BTN") (class "Default")
      (node (ref "J3") (pin "3") (pinfunction "3_3") (pintype "passive"))
      (node (ref "U2") (pin "P$2") (pinfunction "PB13_P$2") (pintype "bidirectional"))
    )
    (net (code "70") (name "TAIL_CTRL") (class "Default")
      (node (ref "R22") (pin "1") (pinfunction "1_1") (pintype "passive"))
      (node (ref "U2") (pin "P$15") (pinfunction "PB7_P$15") (pintype "bidirectional"))
      (node (ref "U9") (pin "4") (pinfunction "CTRL_4") (pintype "passive"))
    )
    (net (code "71") (name "V+") (class "Default")
      (node (ref "C11") (pin "1") (pinfunction "1_1") (pintype "passive"))
      (node (ref "C15") (pin "1") (pinfunction "1_1") (pintype "passive"))
      (node (ref "C19") (pin "1") (pinfunction "1_1") (pintype "passive"))
      (node (ref "C23") (pin "1") (pinfunction "1_1") (pintype "passive"))
      (node (ref "C7") (pin "1") (pinfunction "1_1") (pintype "passive"))
      (node (ref "C8") (pin "1") (pinfunction "1_1") (pintype "passive"))
      (node (ref "G2") (pin "4") (pinfunction "S_4") (pintype "passive"))
      (node (ref "J5") (pin "1") (pinfunction "1_1") (pintype "passive"))
      (node (ref "JMP2") (pin "1") (pinfunction "1_1") (pintype "passive"))
      (node (ref "JMP4") (pin "1") (pinfunction "1_1") (pintype "passive"))
      (node (ref "JMP6") (pin "1") (pinfunction "1_1") (pintype "passive"))
      (node (ref "JMP8") (pin "1") (pinfunction "1_1") (pintype "passive"))
      (node (ref "L3") (pin "1") (pinfunction "1_1") (pintype "passive"))
      (node (ref "L5") (pin "1") (pinfunction "1_1") (pintype "passive"))
      (node (ref "L7") (pin "1") (pinfunction "1_1") (pintype "passive"))
      (node (ref "L9") (pin "1") (pinfunction "1_1") (pintype "passive"))
      (node (ref "LED3") (pin "A") (pinfunction "A_A") (pintype "passive"))
      (node (ref "R11") (pin "2") (pinfunction "2_2") (pintype "passive"))
      (node (ref "R28") (pin "E") (pinfunction "E_E") (pintype "passive"))
      (node (ref "R6") (pin "2") (pinfunction "2_2") (pintype "passive"))
      (node (ref "TP2") (pin "TP") (pinfunction "TP_TP") (pintype "input"))
      (node (ref "U11") (pin "6") (pinfunction "VIN_6") (pintype "input"))
      (node (ref "U13") (pin "6") (pinfunction "VIN_6") (pintype "input"))
      (node (ref "U3") (pin "8") (pinfunction "VIN_8") (pintype "bidirectional"))
      (node (ref "U5") (pin "5") (pinfunction "+VS_5") (pintype "input"))
      (node (ref "U7") (pin "6") (pinfunction "VIN_6") (pintype "input"))
      (node (ref "U9") (pin "6") (pinfunction "VIN_6") (pintype "input"))
    )
    (net (code "72") (name "VCC") (class "Default")
      (node (ref "D10") (pin "C") (pinfunction "C_C") (pintype "passive"))
      (node (ref "G1") (pin "1") (pinfunction "D_1") (pintype "passive"))
      (node (ref "G1") (pin "2") (pinfunction "D_2") (pintype "passive"))
      (node (ref "G1") (pin "5") (pinfunction "D_5") (pintype "passive"))
      (node (ref "G1") (pin "6") (pinfunction "D_6") (pintype "passive"))
      (node (ref "J1") (pin "2") (pinfunction "1_2") (pintype "passive"))
    )
    (net (code "73") (name "unconnected-(M2-3V3-Pad3V3OUT)") (class "Default")
      (node (ref "M2") (pin "3V3OUT") (pinfunction "3V3_3V3OUT") (pintype "output"))
    )
    (net (code "74") (name "unconnected-(M2-PadFIX)") (class "Default")
      (node (ref "M2") (pin "FIX") (pinfunction "FIX_FIX") (pintype "output"))
    )
    (net (code "75") (name "unconnected-(M2-PadPPS)") (class "Default")
      (node (ref "M2") (pin "PPS") (pinfunction "PPS_PPS") (pintype "output"))
    )
    (net (code "76") (name "unconnected-(M2-PadVBAT)") (class "Default")
      (node (ref "M2") (pin "VBAT") (pinfunction "VBAT_VBAT") (pintype "bidirectional"))
    )
    (net (code "77") (name "unconnected-(U1-GPIO05-Pad29)") (class "Default")
      (node (ref "U1") (pin "29") (pinfunction "GPIO05_29") (pintype "bidirectional"))
    )
    (net (code "78") (name "unconnected-(U1-GPIO06-Pad31)") (class "Default")
      (node (ref "U1") (pin "31") (pinfunction "GPIO06_31") (pintype "bidirectional"))
    )
    (net (code "79") (name "unconnected-(U1-GPIO12-Pad32)") (class "Default")
      (node (ref "U1") (pin "32") (pinfunction "GPIO12_32") (pintype "bidirectional"))
    )
    (net (code "80") (name "unconnected-(U1-GPIO13-Pad33)") (class "Default")
      (node (ref "U1") (pin "33") (pinfunction "GPIO13_33") (pintype "bidirectional"))
    )
    (net (code "81") (name "unconnected-(U1-GPIO16-Pad36)") (class "Default")
      (node (ref "U1") (pin "36") (pinfunction "GPIO16_36") (pintype "bidirectional"))
    )
    (net (code "82") (name "unconnected-(U1-GPIO17-Pad11)") (class "Default")
      (node (ref "U1") (pin "11") (pinfunction "GPIO17_11") (pintype "bidirectional"))
    )
    (net (code "83") (name "unconnected-(U1-GPIO18-Pad12)") (class "Default")
      (node (ref "U1") (pin "12") (pinfunction "GPIO18_12") (pintype "bidirectional"))
    )
    (net (code "84") (name "unconnected-(U1-GPIO19-Pad35)") (class "Default")
      (node (ref "U1") (pin "35") (pinfunction "GPIO19_35") (pintype "bidirectional"))
    )
    (net (code "85") (name "unconnected-(U1-GPIO20-Pad38)") (class "Default")
      (node (ref "U1") (pin "38") (pinfunction "GPIO20_38") (pintype "bidirectional"))
    )
    (net (code "86") (name "unconnected-(U1-GPIO21-Pad40)") (class "Default")
      (node (ref "U1") (pin "40") (pinfunction "GPIO21_40") (pintype "bidirectional"))
    )
    (net (code "87") (name "unconnected-(U1-GPIO22-Pad15)") (class "Default")
      (node (ref "U1") (pin "15") (pinfunction "GPIO22_15") (pintype "bidirectional"))
    )
    (net (code "88") (name "unconnected-(U1-GPIO23-Pad16)") (class "Default")
      (node (ref "U1") (pin "16") (pinfunction "GPIO23_16") (pintype "bidirectional"))
    )
    (net (code "89") (name "unconnected-(U1-GPIO24-Pad18)") (class "Default")
      (node (ref "U1") (pin "18") (pinfunction "GPIO24_18") (pintype "bidirectional"))
    )
    (net (code "90") (name "unconnected-(U1-GPIO25-Pad22)") (class "Default")
      (node (ref "U1") (pin "22") (pinfunction "GPIO25_22") (pintype "bidirectional"))
    )
    (net (code "91") (name "unconnected-(U1-GPIO26-Pad37)") (class "Default")
      (node (ref "U1") (pin "37") (pinfunction "GPIO26_37") (pintype "bidirectional"))
    )
    (net (code "92") (name "unconnected-(U1-GPIO27-Pad13)") (class "Default")
      (node (ref "U1") (pin "13") (pinfunction "GPIO27_13") (pintype "bidirectional"))
    )
    (net (code "93") (name "unconnected-(U1-ID_SC-Pad28)") (class "Default")
      (node (ref "U1") (pin "28") (pinfunction "ID_SC_28") (pintype "no_connect"))
    )
    (net (code "94") (name "unconnected-(U1-ID_SD-Pad27)") (class "Default")
      (node (ref "U1") (pin "27") (pinfunction "ID_SD_27") (pintype "no_connect"))
    )
    (net (code "95") (name "unconnected-(U1-SCL-Pad5)") (class "Default")
      (node (ref "U1") (pin "5") (pinfunction "SCL_5") (pintype "bidirectional"))
    )
    (net (code "96") (name "unconnected-(U1-SDA-Pad3)") (class "Default")
      (node (ref "U1") (pin "3") (pinfunction "SDA_3") (pintype "bidirectional"))
    )
    (net (code "97") (name "unconnected-(U1-SPI_CE0-Pad24)") (class "Default")
      (node (ref "U1") (pin "24") (pinfunction "SPI_CE0_24") (pintype "bidirectional"))
    )
    (net (code "98") (name "unconnected-(U1-SPI_CE1-Pad26)") (class "Default")
      (node (ref "U1") (pin "26") (pinfunction "SPI_CE1_26") (pintype "bidirectional"))
    )
    (net (code "99") (name "unconnected-(U1-SPI_MISO-Pad21)") (class "Default")
      (node (ref "U1") (pin "21") (pinfunction "SPI_MISO_21") (pintype "bidirectional"))
    )
    (net (code "100") (name "unconnected-(U1-SPI_MOSI-Pad19)") (class "Default")
      (node (ref "U1") (pin "19") (pinfunction "SPI_MOSI_19") (pintype "bidirectional"))
    )
    (net (code "101") (name "unconnected-(U1-SPI_SCLK-Pad23)") (class "Default")
      (node (ref "U1") (pin "23") (pinfunction "SPI_SCLK_23") (pintype "bidirectional"))
    )
    (net (code "102") (name "unconnected-(U2-5V-PadP$18)") (class "Default")
      (node (ref "U2") (pin "P$18") (pinfunction "5V_P$18") (pintype "bidirectional"))
    )
    (net (code "103") (name "unconnected-(U2-PA8-PadP$5)") (class "Default")
      (node (ref "U2") (pin "P$5") (pinfunction "PA8_P$5") (pintype "bidirectional"))
    )
    (net (code "104") (name "unconnected-(U2-PA11-PadP$8)") (class "Default")
      (node (ref "U2") (pin "P$8") (pinfunction "PA11_P$8") (pintype "bidirectional"))
    )
    (net (code "105") (name "unconnected-(U2-PA12-PadP$9)") (class "Default")
      (node (ref "U2") (pin "P$9") (pinfunction "PA12_P$9") (pintype "bidirectional"))
    )
    (net (code "106") (name "unconnected-(U2-PB1-PadP$27)") (class "Default")
      (node (ref "U2") (pin "P$27") (pinfunction "PB1_P$27") (pintype "bidirectional"))
    )
    (net (code "107") (name "unconnected-(U2-PB10-PadP$26)") (class "Default")
      (node (ref "U2") (pin "P$26") (pinfunction "PB10_P$26") (pintype "bidirectional"))
    )
    (net (code "108") (name "unconnected-(U2-PB11-PadP$25)") (class "Default")
      (node (ref "U2") (pin "P$25") (pinfunction "PB11_P$25") (pintype "bidirectional"))
    )
    (net (code "109") (name "unconnected-(U2-PC13-PadP$39)") (class "Default")
      (node (ref "U2") (pin "P$39") (pinfunction "PC13_P$39") (pintype "bidirectional"))
    )
    (net (code "110") (name "unconnected-(U2-PC14-PadP$38)") (class "Default")
      (node (ref "U2") (pin "P$38") (pinfunction "PC14_P$38") (pintype "bidirectional"))
    )
    (net (code "111") (name "unconnected-(U2-PC15-PadP$37)") (class "Default")
      (node (ref "U2") (pin "P$37") (pinfunction "PC15_P$37") (pintype "bidirectional"))
    )
    (net (code "112") (name "unconnected-(U2-RESET-PadP$24)") (class "Default")
      (node (ref "U2") (pin "P$24") (pinfunction "RESET_P$24") (pintype "bidirectional"))
    )
    (net (code "113") (name "unconnected-(U2-VBAT-PadP$40)") (class "Default")
      (node (ref "U2") (pin "P$40") (pinfunction "VBAT_P$40") (pintype "bidirectional"))
    )
    (net (code "114") (name "unconnected-(U4-N.C.-Pad3)") (class "Default")
      (node (ref "U4") (pin "3") (pinfunction "N.C._3") (pintype "passive"))
    )
  )
)
